# ZIF_HIZ_and_Conververter.net
KiCad netlist of a schematic drawn in Altium Designer
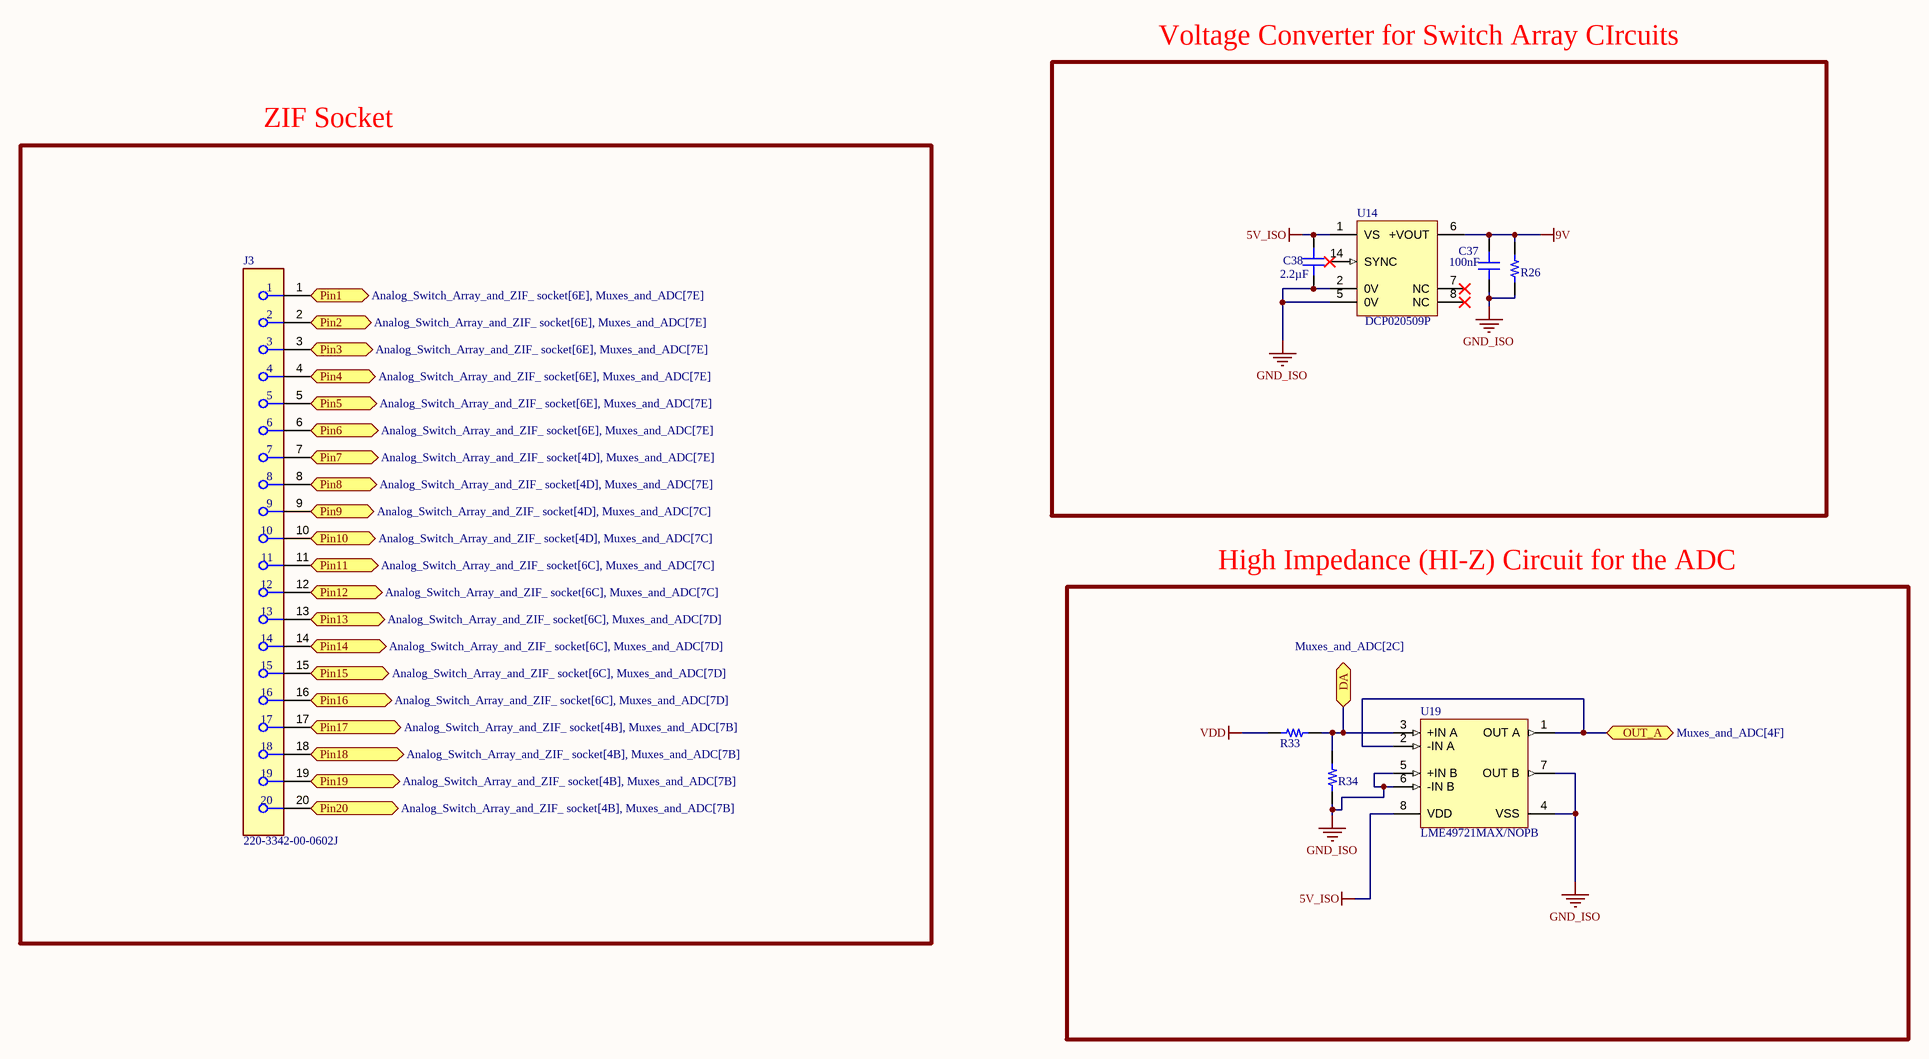
[diagram p0: ZIF_HIZ_and_Conververter.SchDoc]

(export (version "E")
  (design (tool "Eeschema 10.0.6"))
  (components
    (comp (ref "C37")
      (value "100nF")
      (footprint "CAP 1206_3216 - 0.8MM")
      (description "CAP CER 1206 0.1F 16V ULTRA STAB")
      (fields (field (name "PART NUMBER") "C1206X104G4HAC7800"))
      (libsource (lib "University of Massachusetts Lowell") (part "CAPACITOR"))
    )
    (comp (ref "C38")
      (value "2.2µF")
      (footprint "CAP 1206_3216 - 0.8MM")
      (description "CAP CER 2.2UF 25V Y5V 1206")
      (fields (field (name "PART NUMBER") "CC1206ZRY5V8BB225"))
      (libsource (lib "University of Massachusetts Lowell") (part "CAPACITOR"))
    )
    (comp (ref "J3")
      (value "220-3342-00-0602J")
      (footprint "FP-220-3342-00-0602J-0")
      (description "CONN IC DIP SOCKET ZIF 20POS GLD")
      (fields
        (field (name "MANUFACTURER") "3M")
        (field (name "OCTOPART") "https://octopart.com/220-3342-00-0602j-3m-108647")
      )
      (libsource (lib "Altium Content Vault") (part "dba14e038e6f7492952b7f1e871f183"))
    )
    (comp (ref "R26")
      (value "RT1206BRD07125RL")
      (footprint "YAGEO RES 1206_3216")
      (description "RES SMD 125 OHM 0.1% 1/4W 1206")
      (libsource (lib "University of Massachusetts Lowell") (part "RESISTOR"))
    )
    (comp (ref "R33")
      (value "TNPW1206100KBEEA")
      (footprint "RES 1206_3216")
      (description "RES 100K OHM 0.1% 1/4W 1206")
      (libsource (lib "University of Massachusetts Lowell") (part "RESISTOR"))
    )
    (comp (ref "R34")
      (value "TNPW1206100KBEEA")
      (footprint "RES 1206_3216")
      (description "RES 100K OHM 0.1% 1/4W 1206")
      (libsource (lib "University of Massachusetts Lowell") (part "RESISTOR"))
    )
    (comp (ref "U14")
      (value "DCP020509P")
      (footprint "NVA0007A")
      (fields (field (name "MANUFACTURER") "Texas Instruments"))
      (libsource (lib "Altium Content Vault") (part "TI-DCP02XXXNVA7"))
    )
    (comp (ref "U19")
      (value "LME49721MAX/NOPB")
      (footprint "D0008A_L")
      (fields (field (name "MANUFACTURER") "Texas Instruments"))
      (libsource (lib "Altium Content Vault") (part "AMP-AUDA-LME49721-8"))
    )
  )
  (nets
    (net (code "1") (name "/DA") (class "Default")
      (node (ref "R33") (pin "2") (pinfunction "2_2") (pintype "passive"))
      (node (ref "R34") (pin "2") (pinfunction "2_2") (pintype "passive"))
      (node (ref "U19") (pin "3") (pinfunction "+IN_A_3") (pintype "input"))
    )
    (net (code "2") (name "/OUT_A") (class "Default")
      (node (ref "U19") (pin "1") (pinfunction "OUT_A_1") (pintype "output"))
      (node (ref "U19") (pin "2") (pinfunction "-IN_A_2") (pintype "input"))
    )
    (net (code "3") (name "/Pin1") (class "Default")
      (node (ref "J3") (pin "1") (pinfunction "1_1") (pintype "passive"))
    )
    (net (code "4") (name "/Pin2") (class "Default")
      (node (ref "J3") (pin "2") (pinfunction "2_2") (pintype "passive"))
    )
    (net (code "5") (name "/Pin3") (class "Default")
      (node (ref "J3") (pin "3") (pinfunction "3_3") (pintype "passive"))
    )
    (net (code "6") (name "/Pin4") (class "Default")
      (node (ref "J3") (pin "4") (pinfunction "4_4") (pintype "passive"))
    )
    (net (code "7") (name "/Pin5") (class "Default")
      (node (ref "J3") (pin "5") (pinfunction "5_5") (pintype "passive"))
    )
    (net (code "8") (name "/Pin6") (class "Default")
      (node (ref "J3") (pin "6") (pinfunction "6_6") (pintype "passive"))
    )
    (net (code "9") (name "/Pin7") (class "Default")
      (node (ref "J3") (pin "7") (pinfunction "7_7") (pintype "passive"))
    )
    (net (code "10") (name "/Pin8") (class "Default")
      (node (ref "J3") (pin "8") (pinfunction "8_8") (pintype "passive"))
    )
    (net (code "11") (name "/Pin9") (class "Default")
      (node (ref "J3") (pin "9") (pinfunction "9_9") (pintype "passive"))
    )
    (net (code "12") (name "/Pin10") (class "Default")
      (node (ref "J3") (pin "10") (pinfunction "10_10") (pintype "passive"))
    )
    (net (code "13") (name "/Pin11") (class "Default")
      (node (ref "J3") (pin "11") (pinfunction "11_11") (pintype "passive"))
    )
    (net (code "14") (name "/Pin12") (class "Default")
      (node (ref "J3") (pin "12") (pinfunction "12_12") (pintype "passive"))
    )
    (net (code "15") (name "/Pin13") (class "Default")
      (node (ref "J3") (pin "13") (pinfunction "13_13") (pintype "passive"))
    )
    (net (code "16") (name "/Pin14") (class "Default")
      (node (ref "J3") (pin "14") (pinfunction "14_14") (pintype "passive"))
    )
    (net (code "17") (name "/Pin15") (class "Default")
      (node (ref "J3") (pin "15") (pinfunction "15_15") (pintype "passive"))
    )
    (net (code "18") (name "/Pin16") (class "Default")
      (node (ref "J3") (pin "16") (pinfunction "16_16") (pintype "passive"))
    )
    (net (code "19") (name "/Pin17") (class "Default")
      (node (ref "J3") (pin "17") (pinfunction "17_17") (pintype "passive"))
    )
    (net (code "20") (name "/Pin18") (class "Default")
      (node (ref "J3") (pin "18") (pinfunction "18_18") (pintype "passive"))
    )
    (net (code "21") (name "/Pin19") (class "Default")
      (node (ref "J3") (pin "19") (pinfunction "19_19") (pintype "passive"))
    )
    (net (code "22") (name "/Pin20") (class "Default")
      (node (ref "J3") (pin "20") (pinfunction "20_20") (pintype "passive"))
    )
    (net (code "23") (name "5V_ISO") (class "Default")
      (node (ref "C38") (pin "2") (pinfunction "2_2") (pintype "passive"))
      (node (ref "U14") (pin "1") (pinfunction "VS_1") (pintype "power_in"))
      (node (ref "U19") (pin "8") (pinfunction "VDD_8") (pintype "power_in"))
    )
    (net (code "24") (name "9V") (class "Default")
      (node (ref "C37") (pin "2") (pinfunction "2_2") (pintype "passive"))
      (node (ref "R26") (pin "2") (pinfunction "2_2") (pintype "passive"))
      (node (ref "U14") (pin "6") (pinfunction "+VOUT_6") (pintype "power_in"))
    )
    (net (code "25") (name "GND_ISO") (class "Default")
      (node (ref "C37") (pin "1") (pinfunction "1_1") (pintype "passive"))
      (node (ref "C38") (pin "1") (pinfunction "1_1") (pintype "passive"))
      (node (ref "R26") (pin "1") (pinfunction "1_1") (pintype "passive"))
      (node (ref "R34") (pin "1") (pinfunction "1_1") (pintype "passive"))
      (node (ref "U14") (pin "2") (pinfunction "0V_2") (pintype "power_in"))
      (node (ref "U14") (pin "5") (pinfunction "0V_5") (pintype "power_in"))
      (node (ref "U19") (pin "4") (pinfunction "VSS_4") (pintype "power_in"))
      (node (ref "U19") (pin "5") (pinfunction "+IN_B_5") (pintype "input"))
      (node (ref "U19") (pin "6") (pinfunction "-IN_B_6") (pintype "input"))
      (node (ref "U19") (pin "7") (pinfunction "OUT_B_7") (pintype "output"))
    )
    (net (code "26") (name "VDD") (class "Default")
      (node (ref "R33") (pin "1") (pinfunction "1_1") (pintype "passive"))
    )
    (net (code "27") (name "unconnected-(U14-NC-Pad7)") (class "Default")
      (node (ref "U14") (pin "7") (pinfunction "NC_7") (pintype "passive+no_connect"))
    )
    (net (code "28") (name "unconnected-(U14-NC-Pad8)") (class "Default")
      (node (ref "U14") (pin "8") (pinfunction "NC_8") (pintype "passive+no_connect"))
    )
    (net (code "29") (name "unconnected-(U14-SYNC-Pad14)") (class "Default")
      (node (ref "U14") (pin "14") (pinfunction "SYNC_14") (pintype "input+no_connect"))
    )
  )
)
